# BusViewer.net
KiCad netlist of a schematic drawn in Altium Designer
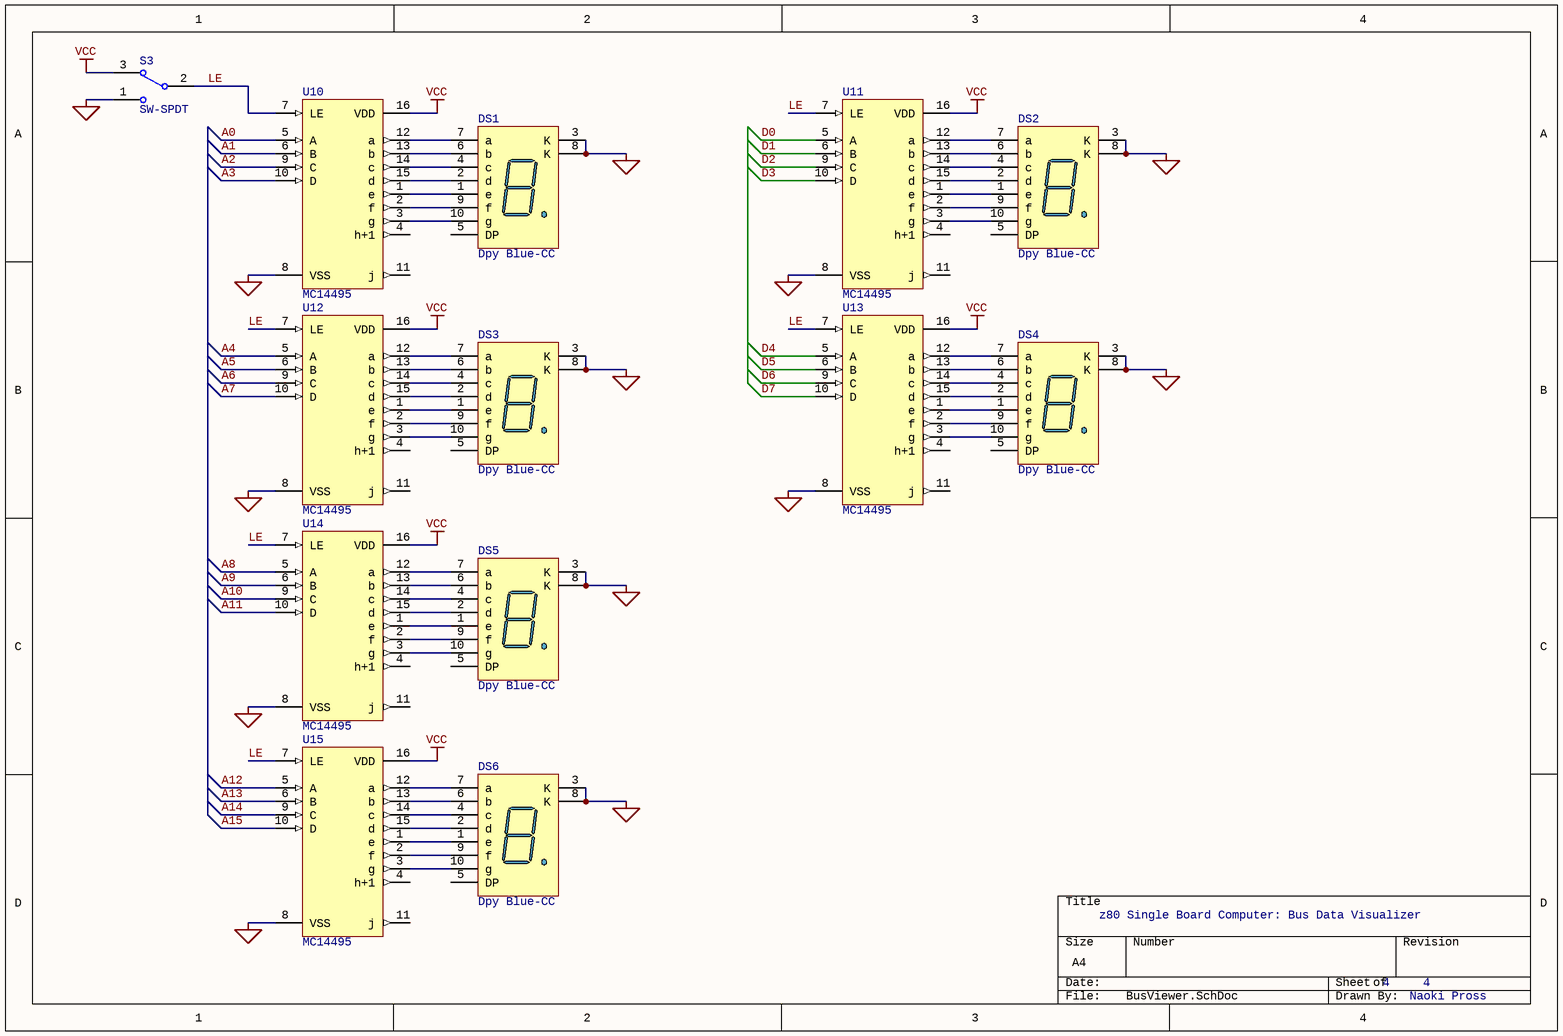
[diagram p0: BusViewer.SchDoc]

(export (version "E")
  (design (tool "Eeschema 10.0.6"))
  (components
    (comp (ref "DS1")
      (value "Dpy Blue-CC")
      (footprint "H")
      (description "14.2 mm General Purpose Blue 7-Segment Display: CC, RH DP, Gray Surface")
      (fields (field (name "PUBLISHER") "Altium Limited"))
      (libsource (lib "Miscellaneous Devices") (part "Dpy Blue-CC"))
    )
    (comp (ref "DS2")
      (value "Dpy Blue-CC")
      (footprint "H")
      (description "14.2 mm General Purpose Blue 7-Segment Display: CC, RH DP, Gray Surface")
      (fields (field (name "PUBLISHER") "Altium Limited"))
      (libsource (lib "Miscellaneous Devices") (part "Dpy Blue-CC"))
    )
    (comp (ref "DS3")
      (value "Dpy Blue-CC")
      (footprint "H")
      (description "14.2 mm General Purpose Blue 7-Segment Display: CC, RH DP, Gray Surface")
      (fields (field (name "PUBLISHER") "Altium Limited"))
      (libsource (lib "Miscellaneous Devices") (part "Dpy Blue-CC"))
    )
    (comp (ref "DS4")
      (value "Dpy Blue-CC")
      (footprint "H")
      (description "14.2 mm General Purpose Blue 7-Segment Display: CC, RH DP, Gray Surface")
      (fields (field (name "PUBLISHER") "Altium Limited"))
      (libsource (lib "Miscellaneous Devices") (part "Dpy Blue-CC"))
    )
    (comp (ref "DS5")
      (value "Dpy Blue-CC")
      (footprint "H")
      (description "14.2 mm General Purpose Blue 7-Segment Display: CC, RH DP, Gray Surface")
      (fields (field (name "PUBLISHER") "Altium Limited"))
      (libsource (lib "Miscellaneous Devices") (part "Dpy Blue-CC"))
    )
    (comp (ref "DS6")
      (value "Dpy Blue-CC")
      (footprint "H")
      (description "14.2 mm General Purpose Blue 7-Segment Display: CC, RH DP, Gray Surface")
      (fields (field (name "PUBLISHER") "Altium Limited"))
      (libsource (lib "Miscellaneous Devices") (part "Dpy Blue-CC"))
    )
    (comp (ref "S3")
      (value "SW-SPDT")
      (footprint "SW_2WAY")
      (description "SPDT Subminiature Toggle Switch, Right Angle Mounting, Vertical Actuation")
      (fields (field (name "PUBLISHER") "Altium Limited"))
      (libsource (lib "Miscellaneous Devices") (part "SW-SPDT"))
    )
    (comp (ref "U10")
      (value "MC14495")
      (footprint "DIP16")
      (description "Hexadecimal to seven segment Latch / Decoder LED Driver")
      (libsource (lib "z80uPC") (part "MC14495"))
    )
    (comp (ref "U11")
      (value "MC14495")
      (footprint "DIP16")
      (description "Hexadecimal to seven segment Latch / Decoder LED Driver")
      (libsource (lib "z80uPC") (part "MC14495"))
    )
    (comp (ref "U12")
      (value "MC14495")
      (footprint "DIP16")
      (description "Hexadecimal to seven segment Latch / Decoder LED Driver")
      (libsource (lib "z80uPC") (part "MC14495"))
    )
    (comp (ref "U13")
      (value "MC14495")
      (footprint "DIP16")
      (description "Hexadecimal to seven segment Latch / Decoder LED Driver")
      (libsource (lib "z80uPC") (part "MC14495"))
    )
    (comp (ref "U14")
      (value "MC14495")
      (footprint "DIP16")
      (description "Hexadecimal to seven segment Latch / Decoder LED Driver")
      (libsource (lib "z80uPC") (part "MC14495"))
    )
    (comp (ref "U15")
      (value "MC14495")
      (footprint "DIP16")
      (description "Hexadecimal to seven segment Latch / Decoder LED Driver")
      (libsource (lib "z80uPC") (part "MC14495"))
    )
  )
  (nets
    (net (code "1") (name "/A0") (class "Default")
      (node (ref "U10") (pin "5") (pinfunction "A_5") (pintype "input"))
    )
    (net (code "2") (name "/A1") (class "Default")
      (node (ref "U10") (pin "6") (pinfunction "B_6") (pintype "input"))
    )
    (net (code "3") (name "/A2") (class "Default")
      (node (ref "U10") (pin "9") (pinfunction "C_9") (pintype "input"))
    )
    (net (code "4") (name "/A3") (class "Default")
      (node (ref "U10") (pin "10") (pinfunction "D_10") (pintype "input"))
    )
    (net (code "5") (name "/A4") (class "Default")
      (node (ref "U12") (pin "5") (pinfunction "A_5") (pintype "input"))
    )
    (net (code "6") (name "/A5") (class "Default")
      (node (ref "U12") (pin "6") (pinfunction "B_6") (pintype "input"))
    )
    (net (code "7") (name "/A6") (class "Default")
      (node (ref "U12") (pin "9") (pinfunction "C_9") (pintype "input"))
    )
    (net (code "8") (name "/A7") (class "Default")
      (node (ref "U12") (pin "10") (pinfunction "D_10") (pintype "input"))
    )
    (net (code "9") (name "/A8") (class "Default")
      (node (ref "U14") (pin "5") (pinfunction "A_5") (pintype "input"))
    )
    (net (code "10") (name "/A9") (class "Default")
      (node (ref "U14") (pin "6") (pinfunction "B_6") (pintype "input"))
    )
    (net (code "11") (name "/A10") (class "Default")
      (node (ref "U14") (pin "9") (pinfunction "C_9") (pintype "input"))
    )
    (net (code "12") (name "/A11") (class "Default")
      (node (ref "U14") (pin "10") (pinfunction "D_10") (pintype "input"))
    )
    (net (code "13") (name "/A12") (class "Default")
      (node (ref "U15") (pin "5") (pinfunction "A_5") (pintype "input"))
    )
    (net (code "14") (name "/A13") (class "Default")
      (node (ref "U15") (pin "6") (pinfunction "B_6") (pintype "input"))
    )
    (net (code "15") (name "/A14") (class "Default")
      (node (ref "U15") (pin "9") (pinfunction "C_9") (pintype "input"))
    )
    (net (code "16") (name "/A15") (class "Default")
      (node (ref "U15") (pin "10") (pinfunction "D_10") (pintype "input"))
    )
    (net (code "17") (name "/D0") (class "Default")
      (node (ref "U11") (pin "5") (pinfunction "A_5") (pintype "input"))
    )
    (net (code "18") (name "/D1") (class "Default")
      (node (ref "U11") (pin "6") (pinfunction "B_6") (pintype "input"))
    )
    (net (code "19") (name "/D2") (class "Default")
      (node (ref "U11") (pin "9") (pinfunction "C_9") (pintype "input"))
    )
    (net (code "20") (name "/D3") (class "Default")
      (node (ref "U11") (pin "10") (pinfunction "D_10") (pintype "input"))
    )
    (net (code "21") (name "/D4") (class "Default")
      (node (ref "U13") (pin "5") (pinfunction "A_5") (pintype "input"))
    )
    (net (code "22") (name "/D5") (class "Default")
      (node (ref "U13") (pin "6") (pinfunction "B_6") (pintype "input"))
    )
    (net (code "23") (name "/D6") (class "Default")
      (node (ref "U13") (pin "9") (pinfunction "C_9") (pintype "input"))
    )
    (net (code "24") (name "/D7") (class "Default")
      (node (ref "U13") (pin "10") (pinfunction "D_10") (pintype "input"))
    )
    (net (code "25") (name "/LE") (class "Default")
      (node (ref "S3") (pin "2") (pinfunction "2_2") (pintype "passive"))
      (node (ref "U10") (pin "7") (pinfunction "LE_7") (pintype "input"))
      (node (ref "U11") (pin "7") (pinfunction "LE_7") (pintype "input"))
      (node (ref "U12") (pin "7") (pinfunction "LE_7") (pintype "input"))
      (node (ref "U13") (pin "7") (pinfunction "LE_7") (pintype "input"))
      (node (ref "U14") (pin "7") (pinfunction "LE_7") (pintype "input"))
      (node (ref "U15") (pin "7") (pinfunction "LE_7") (pintype "input"))
    )
    (net (code "26") (name "GND") (class "Default")
      (node (ref "DS1") (pin "3") (pinfunction "K_3") (pintype "passive"))
      (node (ref "DS1") (pin "8") (pinfunction "K_8") (pintype "passive"))
      (node (ref "DS2") (pin "3") (pinfunction "K_3") (pintype "passive"))
      (node (ref "DS2") (pin "8") (pinfunction "K_8") (pintype "passive"))
      (node (ref "DS3") (pin "3") (pinfunction "K_3") (pintype "passive"))
      (node (ref "DS3") (pin "8") (pinfunction "K_8") (pintype "passive"))
      (node (ref "DS4") (pin "3") (pinfunction "K_3") (pintype "passive"))
      (node (ref "DS4") (pin "8") (pinfunction "K_8") (pintype "passive"))
      (node (ref "DS5") (pin "3") (pinfunction "K_3") (pintype "passive"))
      (node (ref "DS5") (pin "8") (pinfunction "K_8") (pintype "passive"))
      (node (ref "DS6") (pin "3") (pinfunction "K_3") (pintype "passive"))
      (node (ref "DS6") (pin "8") (pinfunction "K_8") (pintype "passive"))
      (node (ref "S3") (pin "1") (pinfunction "1_1") (pintype "passive"))
      (node (ref "U10") (pin "8") (pinfunction "VSS_8") (pintype "passive"))
      (node (ref "U11") (pin "8") (pinfunction "VSS_8") (pintype "passive"))
      (node (ref "U12") (pin "8") (pinfunction "VSS_8") (pintype "passive"))
      (node (ref "U13") (pin "8") (pinfunction "VSS_8") (pintype "passive"))
      (node (ref "U14") (pin "8") (pinfunction "VSS_8") (pintype "passive"))
      (node (ref "U15") (pin "8") (pinfunction "VSS_8") (pintype "passive"))
    )
    (net (code "27") (name "Net-(DS1-a)") (class "Default")
      (node (ref "DS1") (pin "7") (pinfunction "a_7") (pintype "passive"))
      (node (ref "U10") (pin "12") (pinfunction "a_12") (pintype "output"))
    )
    (net (code "28") (name "Net-(DS1-b)") (class "Default")
      (node (ref "DS1") (pin "6") (pinfunction "b_6") (pintype "passive"))
      (node (ref "U10") (pin "13") (pinfunction "b_13") (pintype "output"))
    )
    (net (code "29") (name "Net-(DS1-c)") (class "Default")
      (node (ref "DS1") (pin "4") (pinfunction "c_4") (pintype "passive"))
      (node (ref "U10") (pin "14") (pinfunction "c_14") (pintype "output"))
    )
    (net (code "30") (name "Net-(DS1-d)") (class "Default")
      (node (ref "DS1") (pin "2") (pinfunction "d_2") (pintype "passive"))
      (node (ref "U10") (pin "15") (pinfunction "d_15") (pintype "output"))
    )
    (net (code "31") (name "Net-(DS1-e)") (class "Default")
      (node (ref "DS1") (pin "1") (pinfunction "e_1") (pintype "passive"))
      (node (ref "U10") (pin "1") (pinfunction "e_1") (pintype "output"))
    )
    (net (code "32") (name "Net-(DS1-f)") (class "Default")
      (node (ref "DS1") (pin "9") (pinfunction "f_9") (pintype "passive"))
      (node (ref "U10") (pin "2") (pinfunction "f_2") (pintype "output"))
    )
    (net (code "33") (name "Net-(DS1-g)") (class "Default")
      (node (ref "DS1") (pin "10") (pinfunction "g_10") (pintype "passive"))
      (node (ref "U10") (pin "3") (pinfunction "g_3") (pintype "output"))
    )
    (net (code "34") (name "Net-(DS2-a)") (class "Default")
      (node (ref "DS2") (pin "7") (pinfunction "a_7") (pintype "passive"))
      (node (ref "U11") (pin "12") (pinfunction "a_12") (pintype "output"))
    )
    (net (code "35") (name "Net-(DS2-b)") (class "Default")
      (node (ref "DS2") (pin "6") (pinfunction "b_6") (pintype "passive"))
      (node (ref "U11") (pin "13") (pinfunction "b_13") (pintype "output"))
    )
    (net (code "36") (name "Net-(DS2-c)") (class "Default")
      (node (ref "DS2") (pin "4") (pinfunction "c_4") (pintype "passive"))
      (node (ref "U11") (pin "14") (pinfunction "c_14") (pintype "output"))
    )
    (net (code "37") (name "Net-(DS2-d)") (class "Default")
      (node (ref "DS2") (pin "2") (pinfunction "d_2") (pintype "passive"))
      (node (ref "U11") (pin "15") (pinfunction "d_15") (pintype "output"))
    )
    (net (code "38") (name "Net-(DS2-e)") (class "Default")
      (node (ref "DS2") (pin "1") (pinfunction "e_1") (pintype "passive"))
      (node (ref "U11") (pin "1") (pinfunction "e_1") (pintype "output"))
    )
    (net (code "39") (name "Net-(DS2-f)") (class "Default")
      (node (ref "DS2") (pin "9") (pinfunction "f_9") (pintype "passive"))
      (node (ref "U11") (pin "2") (pinfunction "f_2") (pintype "output"))
    )
    (net (code "40") (name "Net-(DS2-g)") (class "Default")
      (node (ref "DS2") (pin "10") (pinfunction "g_10") (pintype "passive"))
      (node (ref "U11") (pin "3") (pinfunction "g_3") (pintype "output"))
    )
    (net (code "41") (name "Net-(DS3-a)") (class "Default")
      (node (ref "DS3") (pin "7") (pinfunction "a_7") (pintype "passive"))
      (node (ref "U12") (pin "12") (pinfunction "a_12") (pintype "output"))
    )
    (net (code "42") (name "Net-(DS3-b)") (class "Default")
      (node (ref "DS3") (pin "6") (pinfunction "b_6") (pintype "passive"))
      (node (ref "U12") (pin "13") (pinfunction "b_13") (pintype "output"))
    )
    (net (code "43") (name "Net-(DS3-c)") (class "Default")
      (node (ref "DS3") (pin "4") (pinfunction "c_4") (pintype "passive"))
      (node (ref "U12") (pin "14") (pinfunction "c_14") (pintype "output"))
    )
    (net (code "44") (name "Net-(DS3-d)") (class "Default")
      (node (ref "DS3") (pin "2") (pinfunction "d_2") (pintype "passive"))
      (node (ref "U12") (pin "15") (pinfunction "d_15") (pintype "output"))
    )
    (net (code "45") (name "Net-(DS3-e)") (class "Default")
      (node (ref "DS3") (pin "1") (pinfunction "e_1") (pintype "passive"))
      (node (ref "U12") (pin "1") (pinfunction "e_1") (pintype "output"))
    )
    (net (code "46") (name "Net-(DS3-f)") (class "Default")
      (node (ref "DS3") (pin "9") (pinfunction "f_9") (pintype "passive"))
      (node (ref "U12") (pin "2") (pinfunction "f_2") (pintype "output"))
    )
    (net (code "47") (name "Net-(DS3-g)") (class "Default")
      (node (ref "DS3") (pin "10") (pinfunction "g_10") (pintype "passive"))
      (node (ref "U12") (pin "3") (pinfunction "g_3") (pintype "output"))
    )
    (net (code "48") (name "Net-(DS4-a)") (class "Default")
      (node (ref "DS4") (pin "7") (pinfunction "a_7") (pintype "passive"))
      (node (ref "U13") (pin "12") (pinfunction "a_12") (pintype "output"))
    )
    (net (code "49") (name "Net-(DS4-b)") (class "Default")
      (node (ref "DS4") (pin "6") (pinfunction "b_6") (pintype "passive"))
      (node (ref "U13") (pin "13") (pinfunction "b_13") (pintype "output"))
    )
    (net (code "50") (name "Net-(DS4-c)") (class "Default")
      (node (ref "DS4") (pin "4") (pinfunction "c_4") (pintype "passive"))
      (node (ref "U13") (pin "14") (pinfunction "c_14") (pintype "output"))
    )
    (net (code "51") (name "Net-(DS4-d)") (class "Default")
      (node (ref "DS4") (pin "2") (pinfunction "d_2") (pintype "passive"))
      (node (ref "U13") (pin "15") (pinfunction "d_15") (pintype "output"))
    )
    (net (code "52") (name "Net-(DS4-e)") (class "Default")
      (node (ref "DS4") (pin "1") (pinfunction "e_1") (pintype "passive"))
      (node (ref "U13") (pin "1") (pinfunction "e_1") (pintype "output"))
    )
    (net (code "53") (name "Net-(DS4-f)") (class "Default")
      (node (ref "DS4") (pin "9") (pinfunction "f_9") (pintype "passive"))
      (node (ref "U13") (pin "2") (pinfunction "f_2") (pintype "output"))
    )
    (net (code "54") (name "Net-(DS4-g)") (class "Default")
      (node (ref "DS4") (pin "10") (pinfunction "g_10") (pintype "passive"))
      (node (ref "U13") (pin "3") (pinfunction "g_3") (pintype "output"))
    )
    (net (code "55") (name "Net-(DS5-a)") (class "Default")
      (node (ref "DS5") (pin "7") (pinfunction "a_7") (pintype "passive"))
      (node (ref "U14") (pin "12") (pinfunction "a_12") (pintype "output"))
    )
    (net (code "56") (name "Net-(DS5-b)") (class "Default")
      (node (ref "DS5") (pin "6") (pinfunction "b_6") (pintype "passive"))
      (node (ref "U14") (pin "13") (pinfunction "b_13") (pintype "output"))
    )
    (net (code "57") (name "Net-(DS5-c)") (class "Default")
      (node (ref "DS5") (pin "4") (pinfunction "c_4") (pintype "passive"))
      (node (ref "U14") (pin "14") (pinfunction "c_14") (pintype "output"))
    )
    (net (code "58") (name "Net-(DS5-d)") (class "Default")
      (node (ref "DS5") (pin "2") (pinfunction "d_2") (pintype "passive"))
      (node (ref "U14") (pin "15") (pinfunction "d_15") (pintype "output"))
    )
    (net (code "59") (name "Net-(DS5-e)") (class "Default")
      (node (ref "DS5") (pin "1") (pinfunction "e_1") (pintype "passive"))
      (node (ref "U14") (pin "1") (pinfunction "e_1") (pintype "output"))
    )
    (net (code "60") (name "Net-(DS5-f)") (class "Default")
      (node (ref "DS5") (pin "9") (pinfunction "f_9") (pintype "passive"))
      (node (ref "U14") (pin "2") (pinfunction "f_2") (pintype "output"))
    )
    (net (code "61") (name "Net-(DS5-g)") (class "Default")
      (node (ref "DS5") (pin "10") (pinfunction "g_10") (pintype "passive"))
      (node (ref "U14") (pin "3") (pinfunction "g_3") (pintype "output"))
    )
    (net (code "62") (name "Net-(DS6-a)") (class "Default")
      (node (ref "DS6") (pin "7") (pinfunction "a_7") (pintype "passive"))
      (node (ref "U15") (pin "12") (pinfunction "a_12") (pintype "output"))
    )
    (net (code "63") (name "Net-(DS6-b)") (class "Default")
      (node (ref "DS6") (pin "6") (pinfunction "b_6") (pintype "passive"))
      (node (ref "U15") (pin "13") (pinfunction "b_13") (pintype "output"))
    )
    (net (code "64") (name "Net-(DS6-c)") (class "Default")
      (node (ref "DS6") (pin "4") (pinfunction "c_4") (pintype "passive"))
      (node (ref "U15") (pin "14") (pinfunction "c_14") (pintype "output"))
    )
    (net (code "65") (name "Net-(DS6-d)") (class "Default")
      (node (ref "DS6") (pin "2") (pinfunction "d_2") (pintype "passive"))
      (node (ref "U15") (pin "15") (pinfunction "d_15") (pintype "output"))
    )
    (net (code "66") (name "Net-(DS6-e)") (class "Default")
      (node (ref "DS6") (pin "1") (pinfunction "e_1") (pintype "passive"))
      (node (ref "U15") (pin "1") (pinfunction "e_1") (pintype "output"))
    )
    (net (code "67") (name "Net-(DS6-f)") (class "Default")
      (node (ref "DS6") (pin "9") (pinfunction "f_9") (pintype "passive"))
      (node (ref "U15") (pin "2") (pinfunction "f_2") (pintype "output"))
    )
    (net (code "68") (name "Net-(DS6-g)") (class "Default")
      (node (ref "DS6") (pin "10") (pinfunction "g_10") (pintype "passive"))
      (node (ref "U15") (pin "3") (pinfunction "g_3") (pintype "output"))
    )
    (net (code "69") (name "VCC") (class "Default")
      (node (ref "S3") (pin "3") (pinfunction "3_3") (pintype "passive"))
      (node (ref "U10") (pin "16") (pinfunction "VDD_16") (pintype "passive"))
      (node (ref "U11") (pin "16") (pinfunction "VDD_16") (pintype "passive"))
      (node (ref "U12") (pin "16") (pinfunction "VDD_16") (pintype "passive"))
      (node (ref "U13") (pin "16") (pinfunction "VDD_16") (pintype "passive"))
      (node (ref "U14") (pin "16") (pinfunction "VDD_16") (pintype "passive"))
      (node (ref "U15") (pin "16") (pinfunction "VDD_16") (pintype "passive"))
    )
    (net (code "70") (name "unconnected-(DS1-DP-Pad5)") (class "Default")
      (node (ref "DS1") (pin "5") (pinfunction "DP_5") (pintype "passive"))
    )
    (net (code "71") (name "unconnected-(DS2-DP-Pad5)") (class "Default")
      (node (ref "DS2") (pin "5") (pinfunction "DP_5") (pintype "passive"))
    )
    (net (code "72") (name "unconnected-(DS3-DP-Pad5)") (class "Default")
      (node (ref "DS3") (pin "5") (pinfunction "DP_5") (pintype "passive"))
    )
    (net (code "73") (name "unconnected-(DS4-DP-Pad5)") (class "Default")
      (node (ref "DS4") (pin "5") (pinfunction "DP_5") (pintype "passive"))
    )
    (net (code "74") (name "unconnected-(DS5-DP-Pad5)") (class "Default")
      (node (ref "DS5") (pin "5") (pinfunction "DP_5") (pintype "passive"))
    )
    (net (code "75") (name "unconnected-(DS6-DP-Pad5)") (class "Default")
      (node (ref "DS6") (pin "5") (pinfunction "DP_5") (pintype "passive"))
    )
    (net (code "76") (name "unconnected-(U10-h+1-Pad4)") (class "Default")
      (node (ref "U10") (pin "4") (pinfunction "h+1_4") (pintype "output"))
    )
    (net (code "77") (name "unconnected-(U10-j-Pad11)") (class "Default")
      (node (ref "U10") (pin "11") (pinfunction "j_11") (pintype "output"))
    )
    (net (code "78") (name "unconnected-(U11-h+1-Pad4)") (class "Default")
      (node (ref "U11") (pin "4") (pinfunction "h+1_4") (pintype "output"))
    )
    (net (code "79") (name "unconnected-(U11-j-Pad11)") (class "Default")
      (node (ref "U11") (pin "11") (pinfunction "j_11") (pintype "output"))
    )
    (net (code "80") (name "unconnected-(U12-h+1-Pad4)") (class "Default")
      (node (ref "U12") (pin "4") (pinfunction "h+1_4") (pintype "output"))
    )
    (net (code "81") (name "unconnected-(U12-j-Pad11)") (class "Default")
      (node (ref "U12") (pin "11") (pinfunction "j_11") (pintype "output"))
    )
    (net (code "82") (name "unconnected-(U13-h+1-Pad4)") (class "Default")
      (node (ref "U13") (pin "4") (pinfunction "h+1_4") (pintype "output"))
    )
    (net (code "83") (name "unconnected-(U13-j-Pad11)") (class "Default")
      (node (ref "U13") (pin "11") (pinfunction "j_11") (pintype "output"))
    )
    (net (code "84") (name "unconnected-(U14-h+1-Pad4)") (class "Default")
      (node (ref "U14") (pin "4") (pinfunction "h+1_4") (pintype "output"))
    )
    (net (code "85") (name "unconnected-(U14-j-Pad11)") (class "Default")
      (node (ref "U14") (pin "11") (pinfunction "j_11") (pintype "output"))
    )
    (net (code "86") (name "unconnected-(U15-h+1-Pad4)") (class "Default")
      (node (ref "U15") (pin "4") (pinfunction "h+1_4") (pintype "output"))
    )
    (net (code "87") (name "unconnected-(U15-j-Pad11)") (class "Default")
      (node (ref "U15") (pin "11") (pinfunction "j_11") (pintype "output"))
    )
  )
)
